# SCH_teganganrendah_2024-07-17.net
KiCad netlist of a schematic drawn in EasyEDA
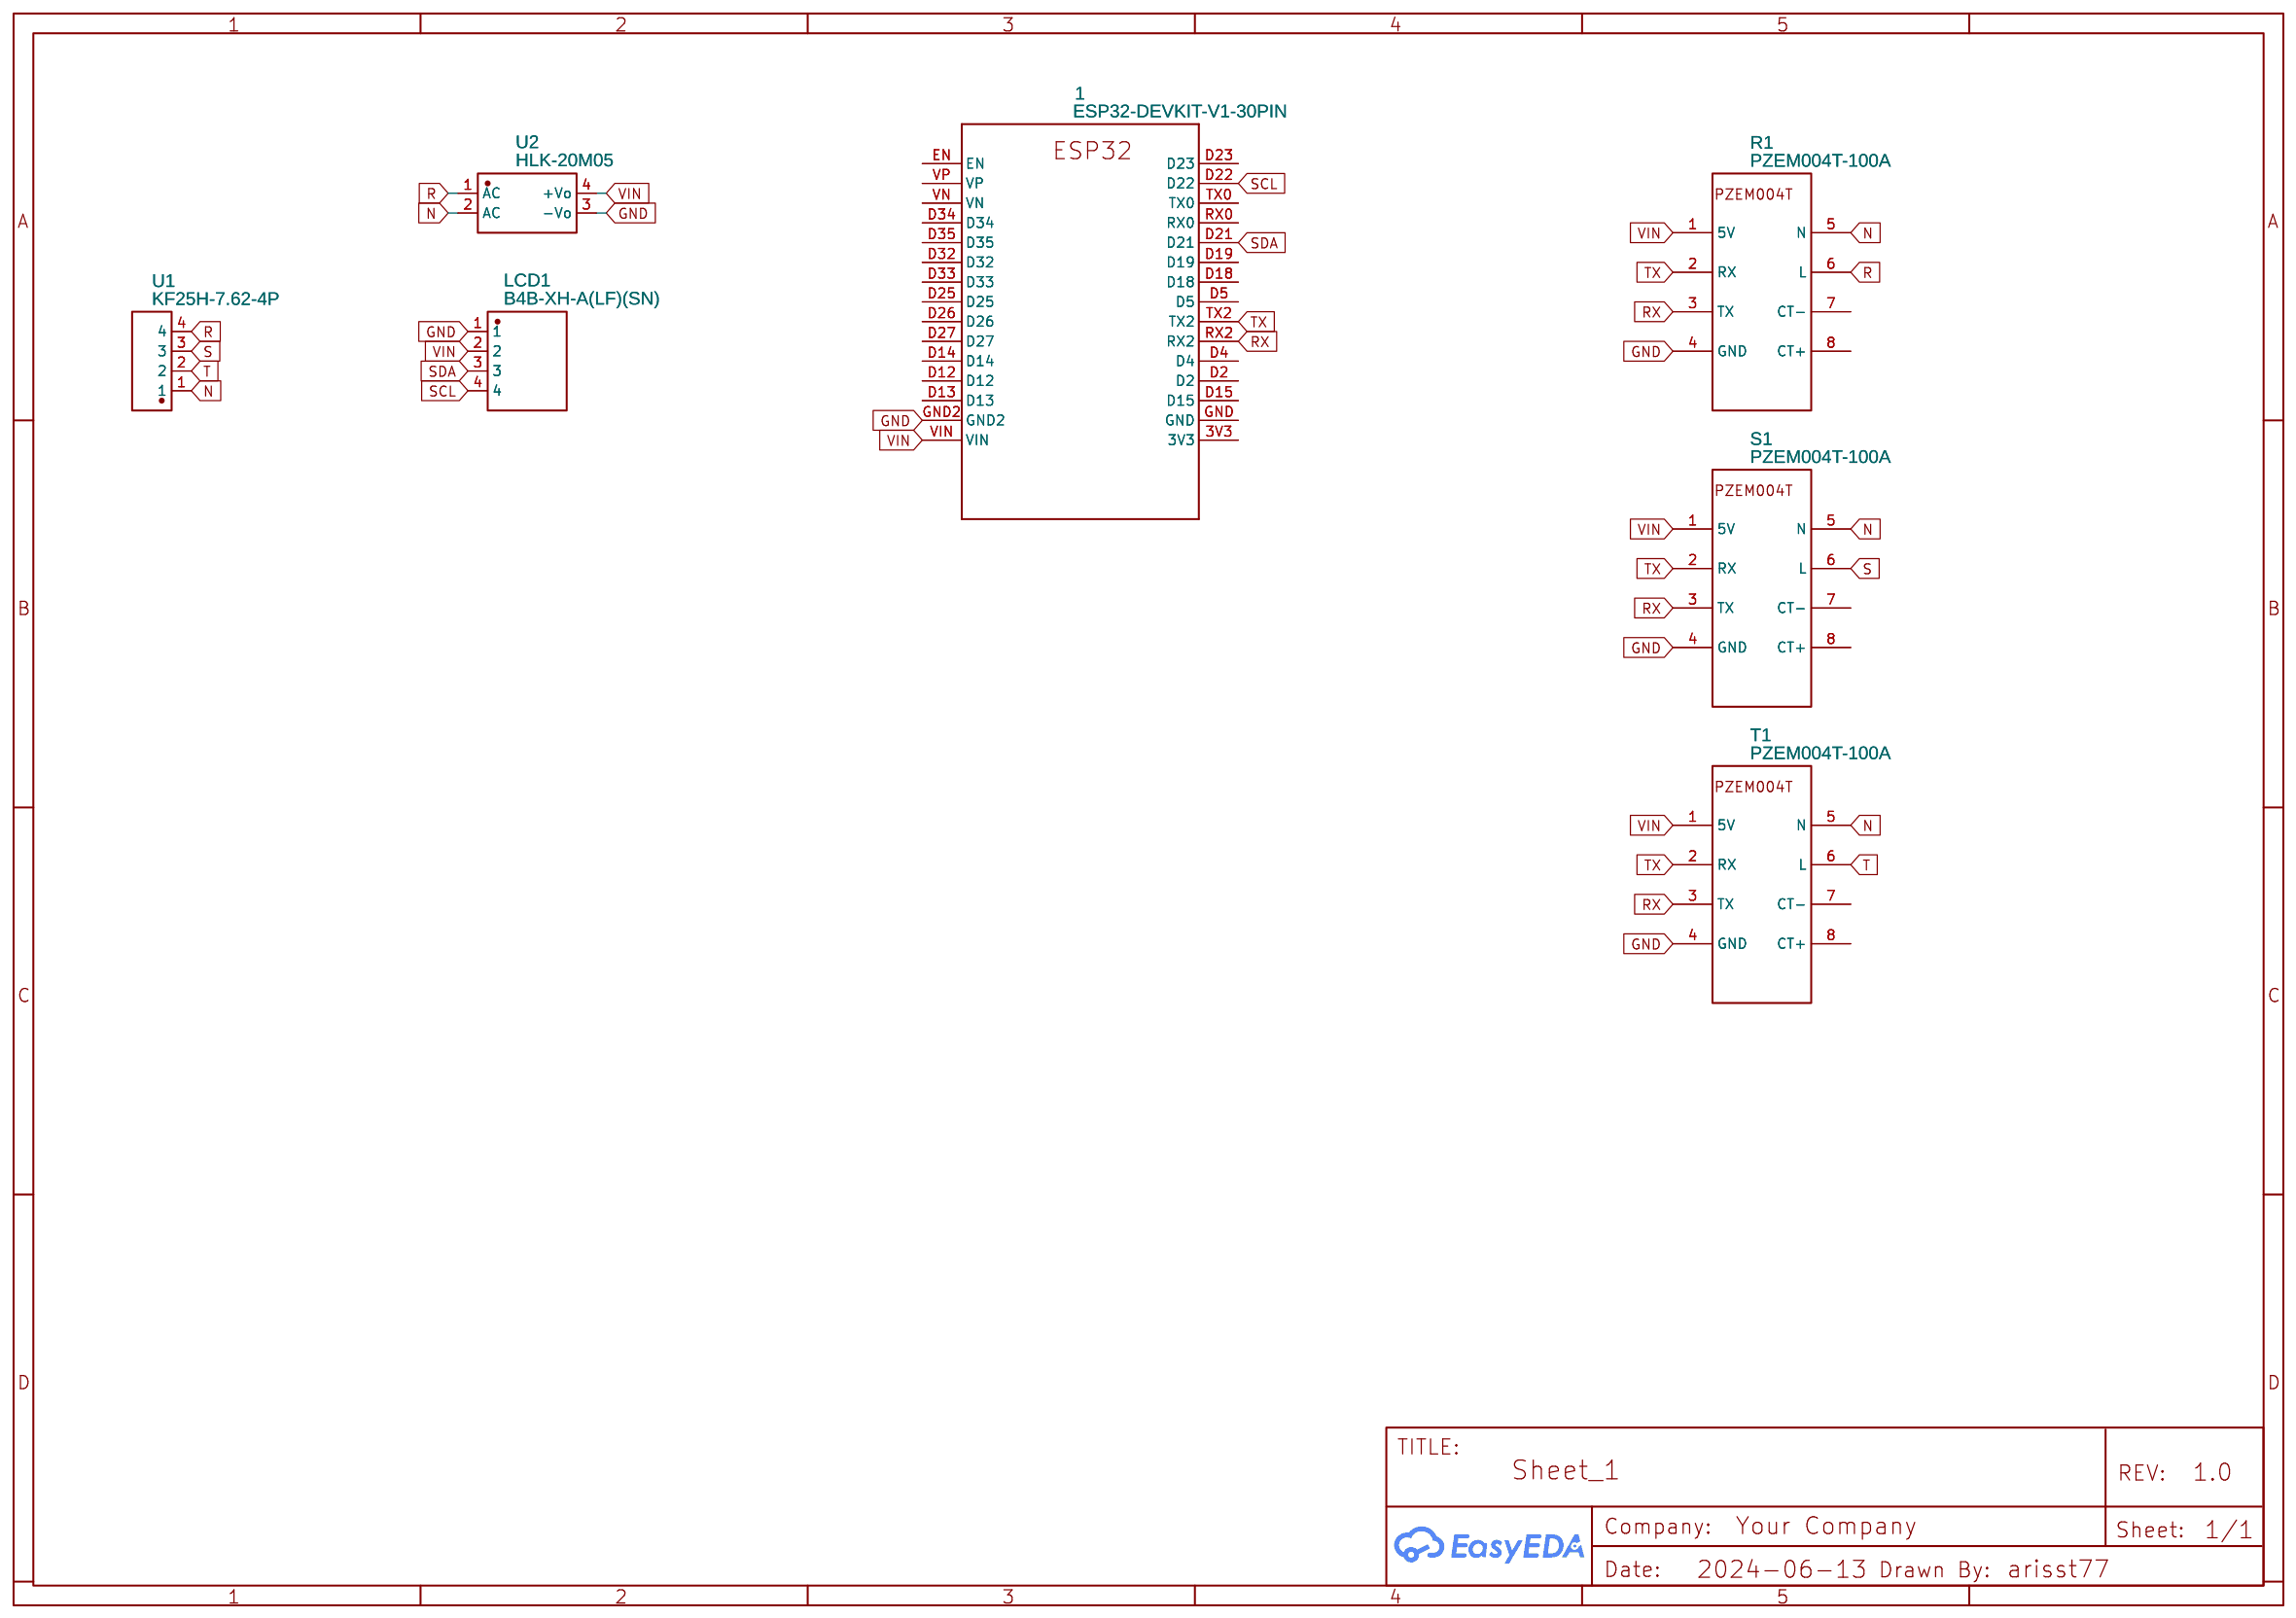
[diagram p0: schematic sheet]

(export (version "E")
  (design (tool "Eeschema 10.0.6"))
  (components
    (comp (ref "1") (value "ESP32-DEVKIT-V1-30PIN") (libsource (lib "") (part "ESP32-DEVKIT-V1-30PIN")))
    (comp (ref "LCD1")
      (value "B4B-XH-A(LF)(SN)")
      (fields (field (name "Manufacturer") "JST"))
      (libsource (lib "") (part "B4B-XH-A(LF)(SN)"))
    )
    (comp (ref "R1")
      (value "PZEM004T-100A")
      (fields (field (name "Manufacturer") "Peacefair"))
      (libsource (lib "") (part "PZEM004T-100A"))
    )
    (comp (ref "S1")
      (value "PZEM004T-100A")
      (fields (field (name "Manufacturer") "Peacefair"))
      (libsource (lib "") (part "PZEM004T-100A_1"))
    )
    (comp (ref "T1")
      (value "PZEM004T-100A")
      (fields (field (name "Manufacturer") "Peacefair"))
      (libsource (lib "") (part "PZEM004T-100A_2"))
    )
    (comp (ref "U1")
      (value "KF25H-7.62-4P")
      (fields (field (name "Manufacturer") "KEFA(科发)"))
      (libsource (lib "") (part "KF25H-7.62-4P"))
    )
    (comp (ref "U2")
      (value "HLK-20M05")
      (fields (field (name "Manufacturer") "HI-LINK(海凌科)"))
      (libsource (lib "") (part "HLK-20M05"))
    )
  )
  (nets
    (net (code "1") (name "GND") (class "Default")
      (node (ref "1") (pin "GND2") (pinfunction "GND2_GND2") (pintype "unspecified"))
      (node (ref "LCD1") (pin "1") (pinfunction "1_1") (pintype "unspecified"))
      (node (ref "R1") (pin "4") (pinfunction "GND_4") (pintype "unspecified"))
      (node (ref "S1") (pin "4") (pinfunction "GND_4") (pintype "unspecified"))
      (node (ref "T1") (pin "4") (pinfunction "GND_4") (pintype "unspecified"))
      (node (ref "U2") (pin "3") (pinfunction "-Vo_3") (pintype "unspecified"))
    )
    (net (code "2") (name "N") (class "Default")
      (node (ref "R1") (pin "5") (pinfunction "N_5") (pintype "unspecified"))
      (node (ref "S1") (pin "5") (pinfunction "N_5") (pintype "unspecified"))
      (node (ref "T1") (pin "5") (pinfunction "N_5") (pintype "unspecified"))
      (node (ref "U1") (pin "1") (pinfunction "1_1") (pintype "unspecified"))
      (node (ref "U2") (pin "2") (pinfunction "AC_2") (pintype "unspecified"))
    )
    (net (code "3") (name "R") (class "Default")
      (node (ref "R1") (pin "6") (pinfunction "L_6") (pintype "unspecified"))
      (node (ref "U1") (pin "4") (pinfunction "4_4") (pintype "unspecified"))
      (node (ref "U2") (pin "1") (pinfunction "AC_1") (pintype "unspecified"))
    )
    (net (code "4") (name "RX") (class "Default")
      (node (ref "1") (pin "RX2") (pinfunction "RX2_RX2") (pintype "unspecified"))
      (node (ref "R1") (pin "3") (pinfunction "TX_3") (pintype "unspecified"))
      (node (ref "S1") (pin "3") (pinfunction "TX_3") (pintype "unspecified"))
      (node (ref "T1") (pin "3") (pinfunction "TX_3") (pintype "unspecified"))
    )
    (net (code "5") (name "S") (class "Default")
      (node (ref "S1") (pin "6") (pinfunction "L_6") (pintype "unspecified"))
      (node (ref "U1") (pin "3") (pinfunction "3_3") (pintype "unspecified"))
    )
    (net (code "6") (name "SCL") (class "Default")
      (node (ref "1") (pin "D22") (pinfunction "D22_D22") (pintype "unspecified"))
      (node (ref "LCD1") (pin "4") (pinfunction "4_4") (pintype "unspecified"))
    )
    (net (code "7") (name "SDA") (class "Default")
      (node (ref "1") (pin "D21") (pinfunction "D21_D21") (pintype "unspecified"))
      (node (ref "LCD1") (pin "3") (pinfunction "3_3") (pintype "unspecified"))
    )
    (net (code "8") (name "T") (class "Default")
      (node (ref "T1") (pin "6") (pinfunction "L_6") (pintype "unspecified"))
      (node (ref "U1") (pin "2") (pinfunction "2_2") (pintype "unspecified"))
    )
    (net (code "9") (name "TX") (class "Default")
      (node (ref "1") (pin "TX2") (pinfunction "TX2_TX2") (pintype "unspecified"))
      (node (ref "R1") (pin "2") (pinfunction "RX_2") (pintype "unspecified"))
      (node (ref "S1") (pin "2") (pinfunction "RX_2") (pintype "unspecified"))
      (node (ref "T1") (pin "2") (pinfunction "RX_2") (pintype "unspecified"))
    )
    (net (code "10") (name "VIN") (class "Default")
      (node (ref "1") (pin "VIN") (pinfunction "VIN_VIN") (pintype "unspecified"))
      (node (ref "LCD1") (pin "2") (pinfunction "2_2") (pintype "unspecified"))
      (node (ref "R1") (pin "1") (pinfunction "5V_1") (pintype "unspecified"))
      (node (ref "S1") (pin "1") (pinfunction "5V_1") (pintype "unspecified"))
      (node (ref "T1") (pin "1") (pinfunction "5V_1") (pintype "unspecified"))
      (node (ref "U2") (pin "4") (pinfunction "+Vo_4") (pintype "unspecified"))
    )
    (net (code "11") (name "unconnected-(1-Pad3V3)") (class "Default")
      (node (ref "1") (pin "3V3") (pinfunction "3V3_3V3") (pintype "unspecified"))
    )
    (net (code "12") (name "unconnected-(1-PadD2)") (class "Default")
      (node (ref "1") (pin "D2") (pinfunction "D2_D2") (pintype "unspecified"))
    )
    (net (code "13") (name "unconnected-(1-PadD4)") (class "Default")
      (node (ref "1") (pin "D4") (pinfunction "D4_D4") (pintype "unspecified"))
    )
    (net (code "14") (name "unconnected-(1-PadD5)") (class "Default")
      (node (ref "1") (pin "D5") (pinfunction "D5_D5") (pintype "unspecified"))
    )
    (net (code "15") (name "unconnected-(1-PadD12)") (class "Default")
      (node (ref "1") (pin "D12") (pinfunction "D12_D12") (pintype "unspecified"))
    )
    (net (code "16") (name "unconnected-(1-PadD13)") (class "Default")
      (node (ref "1") (pin "D13") (pinfunction "D13_D13") (pintype "unspecified"))
    )
    (net (code "17") (name "unconnected-(1-PadD14)") (class "Default")
      (node (ref "1") (pin "D14") (pinfunction "D14_D14") (pintype "unspecified"))
    )
    (net (code "18") (name "unconnected-(1-PadD15)") (class "Default")
      (node (ref "1") (pin "D15") (pinfunction "D15_D15") (pintype "unspecified"))
    )
    (net (code "19") (name "unconnected-(1-PadD18)") (class "Default")
      (node (ref "1") (pin "D18") (pinfunction "D18_D18") (pintype "unspecified"))
    )
    (net (code "20") (name "unconnected-(1-PadD19)") (class "Default")
      (node (ref "1") (pin "D19") (pinfunction "D19_D19") (pintype "unspecified"))
    )
    (net (code "21") (name "unconnected-(1-PadD23)") (class "Default")
      (node (ref "1") (pin "D23") (pinfunction "D23_D23") (pintype "unspecified"))
    )
    (net (code "22") (name "unconnected-(1-PadD25)") (class "Default")
      (node (ref "1") (pin "D25") (pinfunction "D25_D25") (pintype "unspecified"))
    )
    (net (code "23") (name "unconnected-(1-PadD26)") (class "Default")
      (node (ref "1") (pin "D26") (pinfunction "D26_D26") (pintype "unspecified"))
    )
    (net (code "24") (name "unconnected-(1-PadD27)") (class "Default")
      (node (ref "1") (pin "D27") (pinfunction "D27_D27") (pintype "unspecified"))
    )
    (net (code "25") (name "unconnected-(1-PadD32)") (class "Default")
      (node (ref "1") (pin "D32") (pinfunction "D32_D32") (pintype "unspecified"))
    )
    (net (code "26") (name "unconnected-(1-PadD33)") (class "Default")
      (node (ref "1") (pin "D33") (pinfunction "D33_D33") (pintype "unspecified"))
    )
    (net (code "27") (name "unconnected-(1-PadD34)") (class "Default")
      (node (ref "1") (pin "D34") (pinfunction "D34_D34") (pintype "unspecified"))
    )
    (net (code "28") (name "unconnected-(1-PadD35)") (class "Default")
      (node (ref "1") (pin "D35") (pinfunction "D35_D35") (pintype "unspecified"))
    )
    (net (code "29") (name "unconnected-(1-PadEN)") (class "Default")
      (node (ref "1") (pin "EN") (pinfunction "EN_EN") (pintype "unspecified"))
    )
    (net (code "30") (name "unconnected-(1-PadGND)") (class "Default")
      (node (ref "1") (pin "GND") (pinfunction "GND_GND") (pintype "unspecified"))
    )
    (net (code "31") (name "unconnected-(1-PadRX0)") (class "Default")
      (node (ref "1") (pin "RX0") (pinfunction "RX0_RX0") (pintype "unspecified"))
    )
    (net (code "32") (name "unconnected-(1-PadTX0)") (class "Default")
      (node (ref "1") (pin "TX0") (pinfunction "TX0_TX0") (pintype "unspecified"))
    )
    (net (code "33") (name "unconnected-(1-PadVN)") (class "Default")
      (node (ref "1") (pin "VN") (pinfunction "VN_VN") (pintype "unspecified"))
    )
    (net (code "34") (name "unconnected-(1-PadVP)") (class "Default")
      (node (ref "1") (pin "VP") (pinfunction "VP_VP") (pintype "unspecified"))
    )
    (net (code "35") (name "unconnected-(R1-CT+-Pad8)") (class "Default")
      (node (ref "R1") (pin "8") (pinfunction "CT+_8") (pintype "unspecified"))
    )
    (net (code "36") (name "unconnected-(R1-CT--Pad7)") (class "Default")
      (node (ref "R1") (pin "7") (pinfunction "CT-_7") (pintype "unspecified"))
    )
    (net (code "37") (name "unconnected-(S1-CT+-Pad8)") (class "Default")
      (node (ref "S1") (pin "8") (pinfunction "CT+_8") (pintype "unspecified"))
    )
    (net (code "38") (name "unconnected-(S1-CT--Pad7)") (class "Default")
      (node (ref "S1") (pin "7") (pinfunction "CT-_7") (pintype "unspecified"))
    )
    (net (code "39") (name "unconnected-(T1-CT+-Pad8)") (class "Default")
      (node (ref "T1") (pin "8") (pinfunction "CT+_8") (pintype "unspecified"))
    )
    (net (code "40") (name "unconnected-(T1-CT--Pad7)") (class "Default")
      (node (ref "T1") (pin "7") (pinfunction "CT-_7") (pintype "unspecified"))
    )
  )
)
